# Printrboard.net
KiCad netlist of a schematic drawn in EAGLE
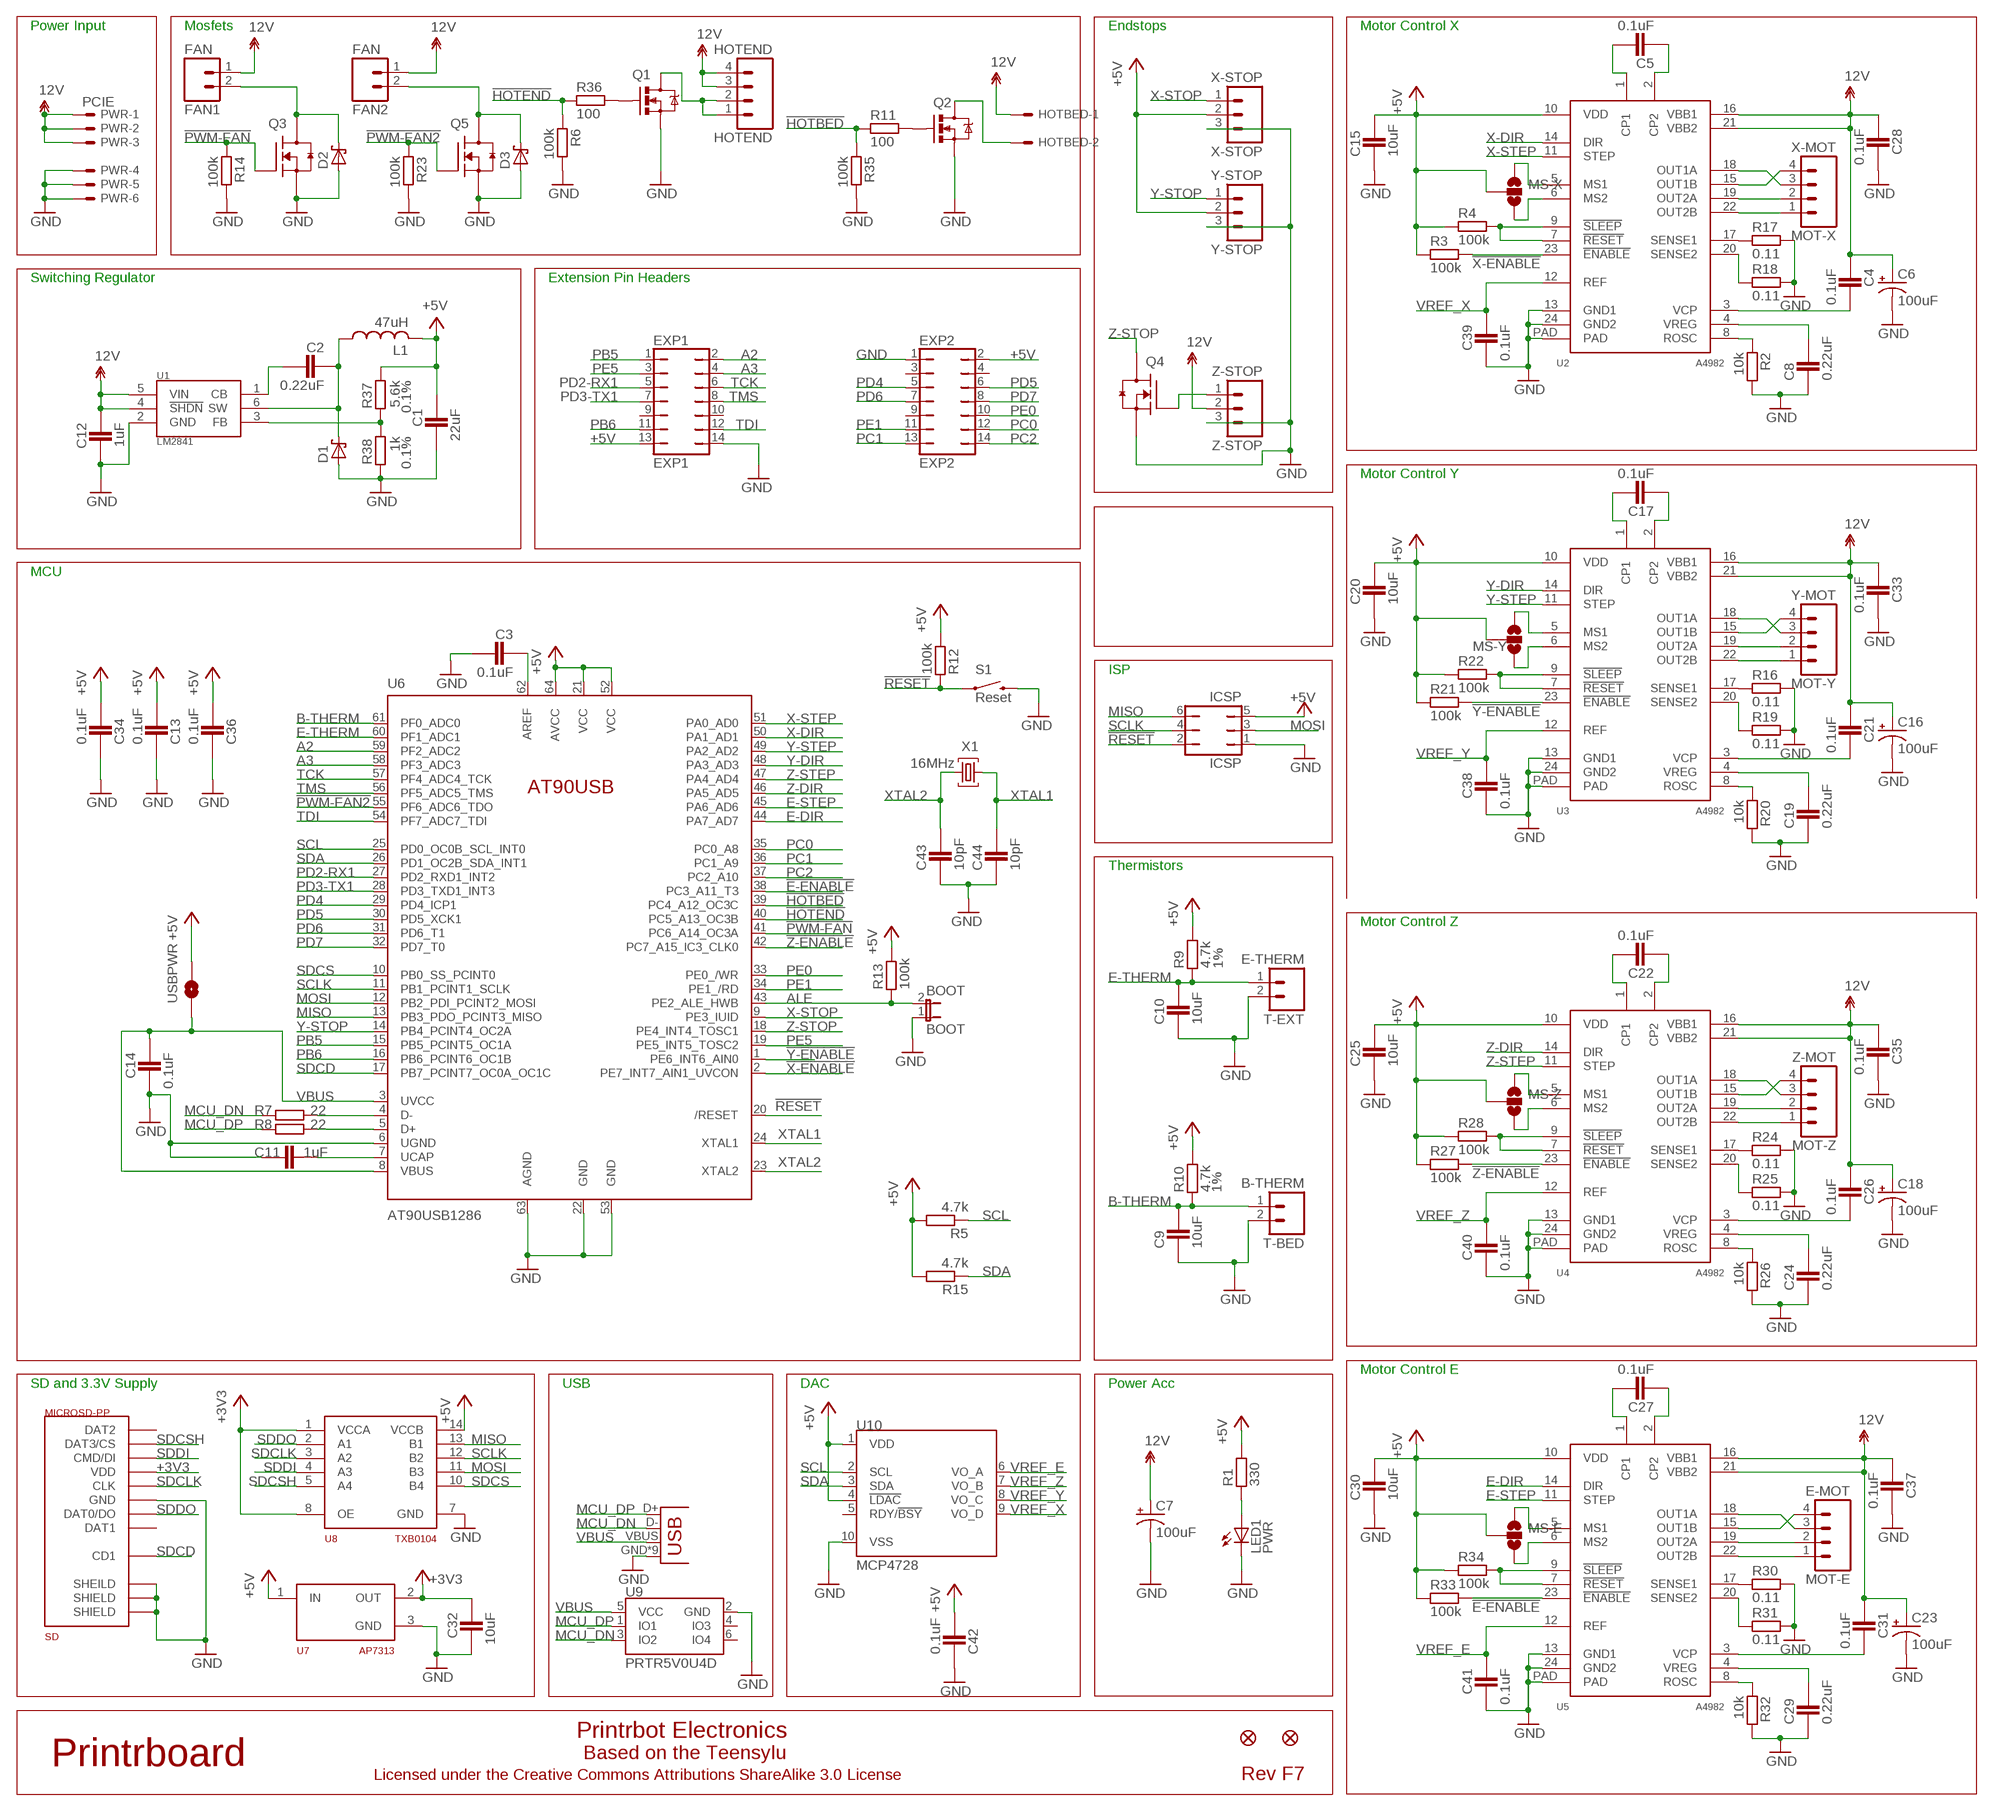
[diagram p0: schematic, sheet 1]

(export (version "E")
  (design (tool "Eeschema 10.0.6"))
  (components
    (comp (ref "BOOT")
      (value "BOOT")
      (footprint "eagle-import:1X02")
      (libsource (lib "eagle-import") (part "JUMPER-2PTH"))
    )
    (comp (ref "C1")
      (value "22uF")
      (footprint "eagle-import:CAPC2012X145AN")
      (libsource (lib "eagle-import") (part "CAPACITOR_0805"))
    )
    (comp (ref "C2")
      (value "0.22uF")
      (footprint "eagle-import:CAPC2012X145AN")
      (libsource (lib "eagle-import") (part "CAPACITOR_0805"))
    )
    (comp (ref "C3")
      (value "0.1uF")
      (footprint "eagle-import:CAPC2012X145AN")
      (libsource (lib "eagle-import") (part "CAPACITOR_0805"))
    )
    (comp (ref "C4")
      (value "0.1uF")
      (footprint "eagle-import:CAPC2012X145AN")
      (libsource (lib "eagle-import") (part "CAPACITOR_0805"))
    )
    (comp (ref "C5")
      (value "0.1uF")
      (footprint "eagle-import:CAPC2012X145AN")
      (libsource (lib "eagle-import") (part "CAPACITOR_0805"))
    )
    (comp (ref "C6")
      (value "100uF")
      (footprint "eagle-import:PANASONIC_D")
      (libsource (lib "eagle-import") (part "CPOL-USD"))
    )
    (comp (ref "C7")
      (value "100uF")
      (footprint "eagle-import:PANASONIC_D")
      (libsource (lib "eagle-import") (part "CPOL-USD"))
    )
    (comp (ref "C8")
      (value "0.22uF")
      (footprint "eagle-import:CAPC2012X145AN")
      (libsource (lib "eagle-import") (part "CAPACITOR_0805"))
    )
    (comp (ref "C9")
      (value "10uF")
      (footprint "eagle-import:CAPC2012X145AN")
      (libsource (lib "eagle-import") (part "CAPACITOR_0805"))
    )
    (comp (ref "C10")
      (value "10uF")
      (footprint "eagle-import:CAPC2012X145AN")
      (libsource (lib "eagle-import") (part "CAPACITOR_0805"))
    )
    (comp (ref "C11")
      (value "1uF")
      (footprint "eagle-import:CAPC2012X145AN")
      (libsource (lib "eagle-import") (part "CAPACITOR_0805"))
    )
    (comp (ref "C12")
      (value "1uF")
      (footprint "eagle-import:CAPC2012X145AN")
      (libsource (lib "eagle-import") (part "CAPACITOR_0805"))
    )
    (comp (ref "C13")
      (value "0.1uF")
      (footprint "eagle-import:CAPC2012X145AN")
      (libsource (lib "eagle-import") (part "CAPACITOR_0805"))
    )
    (comp (ref "C14")
      (value "0.1uF")
      (footprint "eagle-import:CAPC2012X145AN")
      (libsource (lib "eagle-import") (part "CAPACITOR_0805"))
    )
    (comp (ref "C15")
      (value "10uF")
      (footprint "eagle-import:CAPC2012X145AN")
      (libsource (lib "eagle-import") (part "CAPACITOR_0805"))
    )
    (comp (ref "C16")
      (value "100uF")
      (footprint "eagle-import:PANASONIC_D")
      (libsource (lib "eagle-import") (part "CPOL-USD"))
    )
    (comp (ref "C17")
      (value "0.1uF")
      (footprint "eagle-import:CAPC2012X145AN")
      (libsource (lib "eagle-import") (part "CAPACITOR_0805"))
    )
    (comp (ref "C18")
      (value "100uF")
      (footprint "eagle-import:PANASONIC_D")
      (libsource (lib "eagle-import") (part "CPOL-USD"))
    )
    (comp (ref "C19")
      (value "0.22uF")
      (footprint "eagle-import:CAPC2012X145AN")
      (libsource (lib "eagle-import") (part "CAPACITOR_0805"))
    )
    (comp (ref "C20")
      (value "10uF")
      (footprint "eagle-import:CAPC2012X145AN")
      (libsource (lib "eagle-import") (part "CAPACITOR_0805"))
    )
    (comp (ref "C21")
      (value "0.1uF")
      (footprint "eagle-import:CAPC2012X145AN")
      (libsource (lib "eagle-import") (part "CAPACITOR_0805"))
    )
    (comp (ref "C22")
      (value "0.1uF")
      (footprint "eagle-import:CAPC2012X145AN")
      (libsource (lib "eagle-import") (part "CAPACITOR_0805"))
    )
    (comp (ref "C23")
      (value "100uF")
      (footprint "eagle-import:PANASONIC_D")
      (libsource (lib "eagle-import") (part "CPOL-USD"))
    )
    (comp (ref "C24")
      (value "0.22uF")
      (footprint "eagle-import:CAPC2012X145AN")
      (libsource (lib "eagle-import") (part "CAPACITOR_0805"))
    )
    (comp (ref "C25")
      (value "10uF")
      (footprint "eagle-import:CAPC2012X145AN")
      (libsource (lib "eagle-import") (part "CAPACITOR_0805"))
    )
    (comp (ref "C26")
      (value "0.1uF")
      (footprint "eagle-import:CAPC2012X145AN")
      (libsource (lib "eagle-import") (part "CAPACITOR_0805"))
    )
    (comp (ref "C27")
      (value "0.1uF")
      (footprint "eagle-import:CAPC2012X145AN")
      (libsource (lib "eagle-import") (part "CAPACITOR_0805"))
    )
    (comp (ref "C28")
      (value "0.1uF")
      (footprint "eagle-import:CAPC2012X145AN")
      (libsource (lib "eagle-import") (part "CAPACITOR_0805"))
    )
    (comp (ref "C29")
      (value "0.22uF")
      (footprint "eagle-import:CAPC2012X145AN")
      (libsource (lib "eagle-import") (part "CAPACITOR_0805"))
    )
    (comp (ref "C30")
      (value "10uF")
      (footprint "eagle-import:CAPC2012X145AN")
      (libsource (lib "eagle-import") (part "CAPACITOR_0805"))
    )
    (comp (ref "C31")
      (value "0.1uF")
      (footprint "eagle-import:CAPC2012X145AN")
      (libsource (lib "eagle-import") (part "CAPACITOR_0805"))
    )
    (comp (ref "C32")
      (value "10uF")
      (footprint "eagle-import:CAPC2012X145AN")
      (libsource (lib "eagle-import") (part "CAPACITOR_0805"))
    )
    (comp (ref "C33")
      (value "0.1uF")
      (footprint "eagle-import:CAPC2012X145AN")
      (libsource (lib "eagle-import") (part "CAPACITOR_0805"))
    )
    (comp (ref "C34")
      (value "0.1uF")
      (footprint "eagle-import:CAPC2012X145AN")
      (libsource (lib "eagle-import") (part "CAPACITOR_0805"))
    )
    (comp (ref "C35")
      (value "0.1uF")
      (footprint "eagle-import:CAPC2012X145AN")
      (libsource (lib "eagle-import") (part "CAPACITOR_0805"))
    )
    (comp (ref "C36")
      (value "0.1uF")
      (footprint "eagle-import:CAPC2012X145AN")
      (libsource (lib "eagle-import") (part "CAPACITOR_0805"))
    )
    (comp (ref "C37")
      (value "0.1uF")
      (footprint "eagle-import:CAPC2012X145AN")
      (libsource (lib "eagle-import") (part "CAPACITOR_0805"))
    )
    (comp (ref "C38")
      (value "0.1uF")
      (footprint "eagle-import:CAPC2012X145AN")
      (libsource (lib "eagle-import") (part "CAPACITOR_0805"))
    )
    (comp (ref "C39")
      (value "0.1uF")
      (footprint "eagle-import:CAPC2012X145AN")
      (libsource (lib "eagle-import") (part "CAPACITOR_0805"))
    )
    (comp (ref "C40")
      (value "0.1uF")
      (footprint "eagle-import:CAPC2012X145AN")
      (libsource (lib "eagle-import") (part "CAPACITOR_0805"))
    )
    (comp (ref "C41")
      (value "0.1uF")
      (footprint "eagle-import:CAPC2012X145AN")
      (libsource (lib "eagle-import") (part "CAPACITOR_0805"))
    )
    (comp (ref "C42")
      (value "0.1uF")
      (footprint "eagle-import:CAPC2012X145AN")
      (libsource (lib "eagle-import") (part "CAPACITOR_0805"))
    )
    (comp (ref "C43")
      (value "10pF")
      (footprint "eagle-import:CAPC2012X145AN")
      (libsource (lib "eagle-import") (part "CAPACITOR_0805"))
    )
    (comp (ref "C44")
      (value "10pF")
      (footprint "eagle-import:CAPC2012X145AN")
      (libsource (lib "eagle-import") (part "CAPACITOR_0805"))
    )
    (comp (ref "D1")
      (value "SCH-DIODESMA")
      (footprint "eagle-import:SMA")
      (libsource (lib "eagle-import") (part "SCH-DIODESMA"))
    )
    (comp (ref "D2")
      (value "SCH-DIODESMA")
      (footprint "eagle-import:SMA")
      (libsource (lib "eagle-import") (part "SCH-DIODESMA"))
    )
    (comp (ref "D3")
      (value "SCH-DIODESMA")
      (footprint "eagle-import:SMA")
      (libsource (lib "eagle-import") (part "SCH-DIODESMA"))
    )
    (comp (ref "E-MOT")
      (value "MOT-E")
      (footprint "eagle-import:MOLEX-1X4")
      (libsource (lib "eagle-import") (part "M04POLAR"))
    )
    (comp (ref "EXP1")
      (value "EXP1")
      (footprint "eagle-import:JP7Q")
      (libsource (lib "eagle-import") (part "JP7Q"))
    )
    (comp (ref "EXP2")
      (value "EXP2")
      (footprint "eagle-import:JP7Q")
      (libsource (lib "eagle-import") (part "JP7Q"))
    )
    (comp (ref "FAN1")
      (value "FAN")
      (footprint "eagle-import:1X02")
      (libsource (lib "eagle-import") (part "M02PTH"))
    )
    (comp (ref "FAN2")
      (value "FAN")
      (footprint "eagle-import:1X02")
      (libsource (lib "eagle-import") (part "M02PTH"))
    )
    (comp (ref "HOTBED")
      (value "PHOENIX-2POS-5MM-SCREW")
      (footprint "eagle-import:PHOENIX-5MM-2POS")
      (libsource (lib "eagle-import") (part "PHOENIX-2POS-5MM-SCREW"))
    )
    (comp (ref "HOTEND")
      (value "HOTEND")
      (footprint "eagle-import:MOLEX-1X4")
      (libsource (lib "eagle-import") (part "M04POLAR"))
    )
    (comp (ref "ICSP")
      (value "ICSP")
      (footprint "eagle-import:JP3Q")
      (libsource (lib "eagle-import") (part "JP3Q"))
    )
    (comp (ref "JP26")
      (value "FIDUCIAL1X2.5")
      (footprint "eagle-import:FIDUCIAL-1X2.5")
      (libsource (lib "eagle-import") (part "FIDUCIAL1X2.5"))
    )
    (comp (ref "JP33")
      (value "FIDUCIAL1X2.5")
      (footprint "eagle-import:FIDUCIAL-1X2.5")
      (libsource (lib "eagle-import") (part "FIDUCIAL1X2.5"))
    )
    (comp (ref "L1")
      (value "47uH")
      (footprint "eagle-import:SDR1006")
      (libsource (lib "eagle-import") (part "L-US"))
    )
    (comp (ref "LED1")
      (value "PWR")
      (footprint "eagle-import:CHIP-LED0805")
      (libsource (lib "eagle-import") (part "LEDCHIP-LED0805"))
    )
    (comp (ref "MS-E")
      (value "SOLDERJUMPER_2WAYCONNECTED")
      (footprint "eagle-import:SJ_3_CONNECTED")
      (libsource (lib "eagle-import") (part "SOLDERJUMPER_2WAYCONNECTED"))
    )
    (comp (ref "MS-X")
      (value "SOLDERJUMPER_2WAYCONNECTED")
      (footprint "eagle-import:SJ_3_CONNECTED")
      (libsource (lib "eagle-import") (part "SOLDERJUMPER_2WAYCONNECTED"))
    )
    (comp (ref "MS-Y")
      (value "SOLDERJUMPER_2WAYCONNECTED")
      (footprint "eagle-import:SJ_3_CONNECTED")
      (libsource (lib "eagle-import") (part "SOLDERJUMPER_2WAYCONNECTED"))
    )
    (comp (ref "MS-Z")
      (value "SOLDERJUMPER_2WAYCONNECTED")
      (footprint "eagle-import:SJ_3_CONNECTED")
      (libsource (lib "eagle-import") (part "SOLDERJUMPER_2WAYCONNECTED"))
    )
    (comp (ref "PWR")
      (value "PCIE")
      (footprint "eagle-import:5566-6")
      (fields (field (name "MPN") "95566-61002"))
      (libsource (lib "eagle-import") (part "5566-6"))
    )
    (comp (ref "Q1")
      (value "RFP30N06LE")
      (footprint "eagle-import:TO220V")
      (libsource (lib "eagle-import") (part "MOSFET-NCHANNELPTH2"))
    )
    (comp (ref "Q2")
      (value "RFP30N06LE")
      (footprint "eagle-import:TO220V")
      (libsource (lib "eagle-import") (part "MOSFET-NCHANNELPTH2"))
    )
    (comp (ref "Q3")
      (value "RFP30N06LE")
      (footprint "eagle-import:SOT95P280X135-3N")
      (libsource (lib "eagle-import") (part "MOSFET-NCH_SOT-23"))
    )
    (comp (ref "Q4")
      (value "RFP30N06LE")
      (footprint "eagle-import:SOT95P280X135-3N")
      (libsource (lib "eagle-import") (part "MOSFET-NCH_SOT-23"))
    )
    (comp (ref "Q5")
      (value "RFP30N06LE")
      (footprint "eagle-import:SOT95P280X135-3N")
      (libsource (lib "eagle-import") (part "MOSFET-NCH_SOT-23"))
    )
    (comp (ref "R1")
      (value "330")
      (footprint "eagle-import:RESC2012X70N")
      (libsource (lib "eagle-import") (part "RESISTOR_0805"))
    )
    (comp (ref "R2")
      (value "10k")
      (footprint "eagle-import:RESC2012X70N")
      (libsource (lib "eagle-import") (part "RESISTOR_0805"))
    )
    (comp (ref "R3")
      (value "100k")
      (footprint "eagle-import:RESC2012X70N")
      (libsource (lib "eagle-import") (part "RESISTOR_0805"))
    )
    (comp (ref "R4")
      (value "100k")
      (footprint "eagle-import:RESC2012X70N")
      (libsource (lib "eagle-import") (part "RESISTOR_0805"))
    )
    (comp (ref "R5")
      (value "4.7k")
      (footprint "eagle-import:RESC2012X70N")
      (libsource (lib "eagle-import") (part "RESISTOR_0805"))
    )
    (comp (ref "R6")
      (value "100k")
      (footprint "eagle-import:RESC2012X70N")
      (libsource (lib "eagle-import") (part "RESISTOR_0805"))
    )
    (comp (ref "R7")
      (value "22")
      (footprint "eagle-import:RESC2012X70N")
      (libsource (lib "eagle-import") (part "RESISTOR_0805"))
    )
    (comp (ref "R8")
      (value "22")
      (footprint "eagle-import:RESC2012X70N")
      (libsource (lib "eagle-import") (part "RESISTOR_0805"))
    )
    (comp (ref "R9")
      (value "4.7k")
      (footprint "eagle-import:RESC2012X70N")
      (fields (field (name "TOLERANCE") "1%"))
      (libsource (lib "eagle-import") (part "RESISTOR_0805"))
    )
    (comp (ref "R10")
      (value "4.7k")
      (footprint "eagle-import:RESC2012X70N")
      (fields (field (name "TOLERANCE") "1%"))
      (libsource (lib "eagle-import") (part "RESISTOR_0805"))
    )
    (comp (ref "R11")
      (value "100")
      (footprint "eagle-import:RESC2012X70N")
      (libsource (lib "eagle-import") (part "RESISTOR_0805"))
    )
    (comp (ref "R12")
      (value "100k")
      (footprint "eagle-import:RESC2012X70N")
      (libsource (lib "eagle-import") (part "RESISTOR_0805"))
    )
    (comp (ref "R13")
      (value "100k")
      (footprint "eagle-import:RESC2012X70N")
      (libsource (lib "eagle-import") (part "RESISTOR_0805"))
    )
    (comp (ref "R14")
      (value "100k")
      (footprint "eagle-import:RESC2012X70N")
      (libsource (lib "eagle-import") (part "RESISTOR_0805"))
    )
    (comp (ref "R15")
      (value "4.7k")
      (footprint "eagle-import:RESC2012X70N")
      (libsource (lib "eagle-import") (part "RESISTOR_0805"))
    )
    (comp (ref "R16")
      (value "0.11")
      (footprint "eagle-import:RESC2012X70N")
      (libsource (lib "eagle-import") (part "RESISTOR_0805"))
    )
    (comp (ref "R17")
      (value "0.11")
      (footprint "eagle-import:RESC2012X70N")
      (libsource (lib "eagle-import") (part "RESISTOR_0805"))
    )
    (comp (ref "R18")
      (value "0.11")
      (footprint "eagle-import:RESC2012X70N")
      (libsource (lib "eagle-import") (part "RESISTOR_0805"))
    )
    (comp (ref "R19")
      (value "0.11")
      (footprint "eagle-import:RESC2012X70N")
      (libsource (lib "eagle-import") (part "RESISTOR_0805"))
    )
    (comp (ref "R20")
      (value "10k")
      (footprint "eagle-import:RESC2012X70N")
      (libsource (lib "eagle-import") (part "RESISTOR_0805"))
    )
    (comp (ref "R21")
      (value "100k")
      (footprint "eagle-import:RESC2012X70N")
      (libsource (lib "eagle-import") (part "RESISTOR_0805"))
    )
    (comp (ref "R22")
      (value "100k")
      (footprint "eagle-import:RESC2012X70N")
      (libsource (lib "eagle-import") (part "RESISTOR_0805"))
    )
    (comp (ref "R23")
      (value "100k")
      (footprint "eagle-import:RESC2012X70N")
      (libsource (lib "eagle-import") (part "RESISTOR_0805"))
    )
    (comp (ref "R24")
      (value "0.11")
      (footprint "eagle-import:RESC2012X70N")
      (libsource (lib "eagle-import") (part "RESISTOR_0805"))
    )
    (comp (ref "R25")
      (value "0.11")
      (footprint "eagle-import:RESC2012X70N")
      (libsource (lib "eagle-import") (part "RESISTOR_0805"))
    )
    (comp (ref "R26")
      (value "10k")
      (footprint "eagle-import:RESC2012X70N")
      (libsource (lib "eagle-import") (part "RESISTOR_0805"))
    )
    (comp (ref "R27")
      (value "100k")
      (footprint "eagle-import:RESC2012X70N")
      (libsource (lib "eagle-import") (part "RESISTOR_0805"))
    )
    (comp (ref "R28")
      (value "100k")
      (footprint "eagle-import:RESC2012X70N")
      (libsource (lib "eagle-import") (part "RESISTOR_0805"))
    )
    (comp (ref "R30")
      (value "0.11")
      (footprint "eagle-import:RESC2012X70N")
      (libsource (lib "eagle-import") (part "RESISTOR_0805"))
    )
    (comp (ref "R31")
      (value "0.11")
      (footprint "eagle-import:RESC2012X70N")
      (libsource (lib "eagle-import") (part "RESISTOR_0805"))
    )
    (comp (ref "R32")
      (value "10k")
      (footprint "eagle-import:RESC2012X70N")
      (libsource (lib "eagle-import") (part "RESISTOR_0805"))
    )
    (comp (ref "R33")
      (value "100k")
      (footprint "eagle-import:RESC2012X70N")
      (libsource (lib "eagle-import") (part "RESISTOR_0805"))
    )
    (comp (ref "R34")
      (value "100k")
      (footprint "eagle-import:RESC2012X70N")
      (libsource (lib "eagle-import") (part "RESISTOR_0805"))
    )
    (comp (ref "R35")
      (value "100k")
      (footprint "eagle-import:RESC2012X70N")
      (libsource (lib "eagle-import") (part "RESISTOR_0805"))
    )
    (comp (ref "R36")
      (value "100")
      (footprint "eagle-import:RESC2012X70N")
      (libsource (lib "eagle-import") (part "RESISTOR_0805"))
    )
    (comp (ref "R37")
      (value "5.6k")
      (footprint "eagle-import:RESC2012X70N")
      (fields (field (name "TOLERANCE") "0.1%"))
      (libsource (lib "eagle-import") (part "RESISTOR_0805"))
    )
    (comp (ref "R38")
      (value "1k")
      (footprint "eagle-import:RESC2012X70N")
      (fields (field (name "TOLERANCE") "0.1%"))
      (libsource (lib "eagle-import") (part "RESISTOR_0805"))
    )
    (comp (ref "S1")
      (value "Reset")
      (footprint "eagle-import:TACTILE_SWITCH_TALL")
      (libsource (lib "eagle-import") (part "SWITCH-MOMENTARY-2"))
    )
    (comp (ref "SD")
      (value "MICROSD-PP")
      (footprint "eagle-import:USD-101-00660-68-6")
      (libsource (lib "eagle-import") (part "MICROSD-PP"))
    )
    (comp (ref "T-BED")
      (value "B-THERM")
      (footprint "eagle-import:1X02")
      (libsource (lib "eagle-import") (part "M02PTH"))
    )
    (comp (ref "T-EXT")
      (value "E-THERM")
      (footprint "eagle-import:1X02")
      (libsource (lib "eagle-import") (part "M02PTH"))
    )
    (comp (ref "U1")
      (value "LM2841")
      (footprint "eagle-import:TSOT6")
      (libsource (lib "eagle-import") (part "LM2841"))
    )
    (comp (ref "U2")
      (value "A4982")
      (footprint "eagle-import:TSSOP-24")
      (libsource (lib "eagle-import") (part "A4982"))
    )
    (comp (ref "U3")
      (value "A4982")
      (footprint "eagle-import:TSSOP-24")
      (libsource (lib "eagle-import") (part "A4982"))
    )
    (comp (ref "U4")
      (value "A4982")
      (footprint "eagle-import:TSSOP-24")
      (libsource (lib "eagle-import") (part "A4982"))
    )
    (comp (ref "U5")
      (value "A4982")
      (footprint "eagle-import:TSSOP-24")
      (libsource (lib "eagle-import") (part "A4982"))
    )
    (comp (ref "U6")
      (value "AT90USB1286")
      (footprint "eagle-import:TQFP64-2")
      (libsource (lib "eagle-import") (part "AT90USB"))
    )
    (comp (ref "U7")
      (value "AP7313")
      (footprint "eagle-import:SOT23C")
      (libsource (lib "eagle-import") (part "AP7313"))
    )
    (comp (ref "U8")
      (value "TXB0104")
      (footprint "eagle-import:TSSOP14")
      (libsource (lib "eagle-import") (part "TXB0104"))
    )
    (comp (ref "U9")
      (value "PRTR5V0U4D")
      (footprint "eagle-import:SOT23-6")
      (libsource (lib "eagle-import") (part "PRTR5V0U4D"))
    )
    (comp (ref "U10")
      (value "MCP4728")
      (footprint "eagle-import:MSOP10")
      (libsource (lib "eagle-import") (part "MCP4728"))
    )
    (comp (ref "USB-M")
      (value "USB-MICRO-PTH")
      (footprint "eagle-import:USB-MICROB-PTH")
      (libsource (lib "eagle-import") (part "USB-MICRO-PTH"))
    )
    (comp (ref "USBPWR")
      (value "SOLDERJUMPERNO")
      (footprint "eagle-import:SJ_2S-NO")
      (libsource (lib "eagle-import") (part "SOLDERJUMPERNO"))
    )
    (comp (ref "X-MOT")
      (value "MOT-X")
      (footprint "eagle-import:MOLEX-1X4")
      (libsource (lib "eagle-import") (part "M04POLAR"))
    )
    (comp (ref "X-STOP")
      (value "X-STOP")
      (footprint "eagle-import:MOLEX-1X3")
      (libsource (lib "eagle-import") (part "M03POLAR"))
    )
    (comp (ref "X1")
      (value "16MHz")
      (footprint "eagle-import:NDK-XTAL")
      (libsource (lib "eagle-import") (part "XTAL"))
    )
    (comp (ref "Y-MOT")
      (value "MOT-Y")
      (footprint "eagle-import:MOLEX-1X4")
      (libsource (lib "eagle-import") (part "M04POLAR"))
    )
    (comp (ref "Y-STOP")
      (value "Y-STOP")
      (footprint "eagle-import:MOLEX-1X3")
      (libsource (lib "eagle-import") (part "M03POLAR"))
    )
    (comp (ref "Z-MOT")
      (value "MOT-Z")
      (footprint "eagle-import:MOLEX-1X4")
      (libsource (lib "eagle-import") (part "M04POLAR"))
    )
    (comp (ref "Z-STOP")
      (value "Z-STOP")
      (footprint "eagle-import:MOLEX-1X3")
      (libsource (lib "eagle-import") (part "M03POLAR"))
    )
  )
  (nets
    (net (code "1") (name "+3V3") (class "Default")
      (node (ref "C32") (pin "1") (pinfunction "1_1") (pintype "passive"))
      (node (ref "SD") (pin "P$4") (pinfunction "VDD_P$4") (pintype "power_in"))
      (node (ref "U7") (pin "2") (pinfunction "OUT_2") (pintype "power_in"))
      (node (ref "U8") (pin "1") (pinfunction "VCCA_1") (pintype "power_in"))
      (node (ref "U8") (pin "8") (pinfunction "OE_8") (pintype "input"))
    )
    (net (code "2") (name "+5V") (class "Default")
      (node (ref "C1") (pin "1") (pinfunction "1_1") (pintype "passive"))
      (node (ref "C13") (pin "2") (pinfunction "2_2") (pintype "passive"))
      (node (ref "C15") (pin "2") (pinfunction "2_2") (pintype "passive"))
      (node (ref "C20") (pin "2") (pinfunction "2_2") (pintype "passive"))
      (node (ref "C25") (pin "2") (pinfunction "2_2") (pintype "passive"))
      (node (ref "C30") (pin "2") (pinfunction "2_2") (pintype "passive"))
      (node (ref "C34") (pin "2") (pinfunction "2_2") (pintype "passive"))
      (node (ref "C36") (pin "2") (pinfunction "2_2") (pintype "passive"))
      (node (ref "C42") (pin "2") (pinfunction "2_2") (pintype "passive"))
      (node (ref "EXP1") (pin "13") (pinfunction "13_13") (pintype "passive"))
      (node (ref "EXP2") (pin "2") (pinfunction "2_2") (pintype "passive"))
      (node (ref "ICSP") (pin "5") (pinfunction "5_5") (pintype "passive"))
      (node (ref "L1") (pin "P$2") (pinfunction "2_P$2") (pintype "passive"))
      (node (ref "MS-E") (pin "2") (pinfunction "2_2") (pintype "passive"))
      (node (ref "MS-X") (pin "2") (pinfunction "2_2") (pintype "passive"))
      (node (ref "MS-Y") (pin "2") (pinfunction "2_2") (pintype "passive"))
      (node (ref "MS-Z") (pin "2") (pinfunction "2_2") (pintype "passive"))
      (node (ref "R1") (pin "2") (pinfunction "2_2") (pintype "passive"))
      (node (ref "R10") (pin "2") (pinfunction "2_2") (pintype "passive"))
      (node (ref "R12") (pin "2") (pinfunction "2_2") (pintype "passive"))
      (node (ref "R13") (pin "2") (pinfunction "2_2") (pintype "passive"))
      (node (ref "R15") (pin "2") (pinfunction "2_2") (pintype "passive"))
      (node (ref "R21") (pin "1") (pinfunction "1_1") (pintype "passive"))
      (node (ref "R22") (pin "1") (pinfunction "1_1") (pintype "passive"))
      (node (ref "R27") (pin "1") (pinfunction "1_1") (pintype "passive"))
      (node (ref "R28") (pin "1") (pinfunction "1_1") (pintype "passive"))
      (node (ref "R3") (pin "1") (pinfunction "1_1") (pintype "passive"))
      (node (ref "R33") (pin "1") (pinfunction "1_1") (pintype "passive"))
      (node (ref "R34") (pin "1") (pinfunction "1_1") (pintype "passive"))
      (node (ref "R37") (pin "1") (pinfunction "1_1") (pintype "passive"))
      (node (ref "R4") (pin "1") (pinfunction "1_1") (pintype "passive"))
      (node (ref "R5") (pin "2") (pinfunction "2_2") (pintype "passive"))
      (node (ref "R9") (pin "2") (pinfunction "2_2") (pintype "passive"))
      (node (ref "U10") (pin "1") (pinfunction "VDD_1") (pintype "power_in"))
      (node (ref "U10") (pin "4") (pinfunction "~{LDAC}_4") (pintype "input"))
      (node (ref "U2") (pin "10") (pinfunction "VDD_10") (pintype "power_in"))
      (node (ref "U3") (pin "10") (pinfunction "VDD_10") (pintype "power_in"))
      (node (ref "U4") (pin "10") (pinfunction "VDD_10") (pintype "power_in"))
      (node (ref "U5") (pin "10") (pinfunction "VDD_10") (pintype "power_in"))
      (node (ref "U6") (pin "21") (pinfunction "VCC_21") (pintype "power_in"))
      (node (ref "U6") (pin "52") (pinfunction "VCC_52") (pintype "power_in"))
      (node (ref "U6") (pin "64") (pinfunction "AVCC_64") (pintype "power_in"))
      (node (ref "U7") (pin "1") (pinfunction "IN_1") (pintype "power_in"))
      (node (ref "U8") (pin "14") (pinfunction "VCCB_14") (pintype "power_in"))
      (node (ref "USBPWR") (pin "2") (pinfunction "2_2") (pintype "passive"))
      (node (ref "X-STOP") (pin "2") (pinfunction "2_2") (pintype "passive"))
      (node (ref "Y-STOP") (pin "2") (pinfunction "2_2") (pintype "passive"))
    )
    (net (code "3") (name "/A2") (class "Default")
      (node (ref "EXP1") (pin "2") (pinfunction "2_2") (pintype "passive"))
      (node (ref "U6") (pin "59") (pinfunction "PF2_ADC2_59") (pintype "bidirectional"))
    )
    (net (code "4") (name "/A3") (class "Default")
      (node (ref "EXP1") (pin "4") (pinfunction "4_4") (pintype "passive"))
      (node (ref "U6") (pin "58") (pinfunction "PF3_ADC3_58") (pintype "bidirectional"))
    )
    (net (code "5") (name "/ALE") (class "Default")
      (node (ref "BOOT") (pin "2") (pinfunction "2_2") (pintype "passive"))
      (node (ref "R13") (pin "1") (pinfunction "1_1") (pintype "passive"))
      (node (ref "U6") (pin "43") (pinfunction "PE2_ALE_HWB_43") (pintype "bidirectional"))
    )
    (net (code "6") (name "/B-THERM") (class "Default")
      (node (ref "C9") (pin "2") (pinfunction "2_2") (pintype "passive"))
      (node (ref "R10") (pin "1") (pinfunction "1_1") (pintype "passive"))
      (node (ref "T-BED") (pin "1") (pinfunction "1_1") (pintype "passive"))
      (node (ref "U6") (pin "61") (pinfunction "PF0_ADC0_61") (pintype "bidirectional"))
    )
    (net (code "7") (name "/E-DIR") (class "Default")
      (node (ref "U5") (pin "14") (pinfunction "DIR_14") (pintype "input"))
      (node (ref "U6") (pin "44") (pinfunction "PA7_AD7_44") (pintype "bidirectional"))
    )
    (net (code "8") (name "/E-STEP") (class "Default")
      (node (ref "U5") (pin "11") (pinfunction "STEP_11") (pintype "input"))
      (node (ref "U6") (pin "45") (pinfunction "PA6_AD6_45") (pintype "bidirectional"))
    )
    (net (code "9") (name "/E-THERM") (class "Default")
      (node (ref "C10") (pin "2") (pinfunction "2_2") (pintype "passive"))
      (node (ref "R9") (pin "1") (pinfunction "1_1") (pintype "passive"))
      (node (ref "T-EXT") (pin "1") (pinfunction "1_1") (pintype "passive"))
      (node (ref "U6") (pin "60") (pinfunction "PF1_ADC1_60") (pintype "bidirectional"))
    )
    (net (code "10") (name "/MCU_DN") (class "Default")
      (node (ref "R7") (pin "1") (pinfunction "1_1") (pintype "passive"))
      (node (ref "U9") (pin "3") (pinfunction "IO2_3") (pintype "bidirectional"))
      (node (ref "USB-M") (pin "D-") (pinfunction "D-_D-") (pintype "bidirectional"))
    )
    (net (code "11") (name "/MCU_DP") (class "Default")
      (node (ref "R8") (pin "1") (pinfunction "1_1") (pintype "passive"))
      (node (ref "U9") (pin "1") (pinfunction "IO1_1") (pintype "bidirectional"))
      (node (ref "USB-M") (pin "D+") (pinfunction "D+_D+") (pintype "bidirectional"))
    )
    (net (code "12") (name "/MISO") (class "Default")
      (node (ref "ICSP") (pin "6") (pinfunction "6_6") (pintype "passive"))
      (node (ref "U6") (pin "13") (pinfunction "PB3_PDO_PCINT3_MISO_13") (pintype "bidirectional"))
      (node (ref "U8") (pin "13") (pinfunction "B1_13") (pintype "bidirectional"))
    )
    (net (code "13") (name "/MOSI") (class "Default")
      (node (ref "ICSP") (pin "3") (pinfunction "3_3") (pintype "passive"))
      (node (ref "U6") (pin "12") (pinfunction "PB2_PDI_PCINT2_MOSI_12") (pintype "bidirectional"))
      (node (ref "U8") (pin "11") (pinfunction "B3_11") (pintype "bidirectional"))
    )
    (net (code "14") (name "/PB5") (class "Default")
      (node (ref "EXP1") (pin "1") (pinfunction "1_1") (pintype "passive"))
      (node (ref "U6") (pin "15") (pinfunction "PB5_PCINT5_OC1A_15") (pintype "bidirectional"))
    )
    (net (code "15") (name "/PB6") (class "Default")
      (node (ref "EXP1") (pin "11") (pinfunction "11_11") (pintype "passive"))
      (node (ref "U6") (pin "16") (pinfunction "PB6_PCINT6_OC1B_16") (pintype "bidirectional"))
    )
    (net (code "16") (name "/PC0") (class "Default")
      (node (ref "EXP2") (pin "12") (pinfunction "12_12") (pintype "passive"))
      (node (ref "U6") (pin "35") (pinfunction "PC0_A8_35") (pintype "bidirectional"))
    )
    (net (code "17") (name "/PC1") (class "Default")
      (node (ref "EXP2") (pin "13") (pinfunction "13_13") (pintype "passive"))
      (node (ref "U6") (pin "36") (pinfunction "PC1_A9_36") (pintype "bidirectional"))
    )
    (net (code "18") (name "/PC2") (class "Default")
      (node (ref "EXP2") (pin "14") (pinfunction "14_14") (pintype "passive"))
      (node (ref "U6") (pin "37") (pinfunction "PC2_A10_37") (pintype "bidirectional"))
    )
    (net (code "19") (name "/PD2-RX1") (class "Default")
      (node (ref "EXP1") (pin "5") (pinfunction "5_5") (pintype "passive"))
      (node (ref "U6") (pin "27") (pinfunction "PD2_RXD1_INT2_27") (pintype "bidirectional"))
    )
    (net (code "20") (name "/PD3-TX1") (class "Default")
      (node (ref "EXP1") (pin "7") (pinfunction "7_7") (pintype "passive"))
      (node (ref "U6") (pin "28") (pinfunction "PD3_TXD1_INT3_28") (pintype "bidirectional"))
    )
    (net (code "21") (name "/PD4") (class "Default")
      (node (ref "EXP2") (pin "5") (pinfunction "5_5") (pintype "passive"))
      (node (ref "U6") (pin "29") (pinfunction "PD4_ICP1_29") (pintype "bidirectional"))
    )
    (net (code "22") (name "/PD5") (class "Default")
      (node (ref "EXP2") (pin "6") (pinfunction "6_6") (pintype "passive"))
      (node (ref "U6") (pin "30") (pinfunction "PD5_XCK1_30") (pintype "bidirectional"))
    )
    (net (code "23") (name "/PD6") (class "Default")
      (node (ref "EXP2") (pin "7") (pinfunction "7_7") (pintype "passive"))
      (node (ref "U6") (pin "31") (pinfunction "PD6_T1_31") (pintype "bidirectional"))
    )
    (net (code "24") (name "/PD7") (class "Default")
      (node (ref "EXP2") (pin "8") (pinfunction "8_8") (pintype "passive"))
      (node (ref "U6") (pin "32") (pinfunction "PD7_T0_32") (pintype "bidirectional"))
    )
    (net (code "25") (name "/PE0") (class "Default")
      (node (ref "EXP2") (pin "10") (pinfunction "10_10") (pintype "passive"))
      (node (ref "U6") (pin "33") (pinfunction "PE0_/WR_33") (pintype "bidirectional"))
    )
    (net (code "26") (name "/PE1") (class "Default")
      (node (ref "EXP2") (pin "11") (pinfunction "11_11") (pintype "passive"))
      (node (ref "U6") (pin "34") (pinfunction "PE1_/RD_34") (pintype "bidirectional"))
    )
    (net (code "27") (name "/PE5") (class "Default")
      (node (ref "EXP1") (pin "3") (pinfunction "3_3") (pintype "passive"))
      (node (ref "U6") (pin "19") (pinfunction "PE5_INT5_TOSC2_19") (pintype "bidirectional"))
    )
    (net (code "28") (name "/SCL") (class "Default")
      (node (ref "R5") (pin "1") (pinfunction "1_1") (pintype "passive"))
      (node (ref "U10") (pin "2") (pinfunction "SCL_2") (pintype "input"))
      (node (ref "U6") (pin "25") (pinfunction "PD0_OC0B_SCL_INT0_25") (pintype "bidirectional"))
    )
    (net (code "29") (name "/SCLK") (class "Default")
      (node (ref "ICSP") (pin "4") (pinfunction "4_4") (pintype "passive"))
      (node (ref "U6") (pin "11") (pinfunction "PB1_PCINT1_SCLK_11") (pintype "bidirectional"))
      (node (ref "U8") (pin "12") (pinfunction "B2_12") (pintype "bidirectional"))
    )
    (net (code "30") (name "/SDA") (class "Default")
      (node (ref "R15") (pin "1") (pinfunction "1_1") (pintype "passive"))
      (node (ref "U10") (pin "3") (pinfunction "SDA_3") (pintype "bidirectional"))
      (node (ref "U6") (pin "26") (pinfunction "PD1_OC2B_SDA_INT1_26") (pintype "bidirectional"))
    )
    (net (code "31") (name "/SDCD") (class "Default")
      (node (ref "SD") (pin "CD") (pinfunction "CD1_CD") (pintype "bidirectional"))
      (node (ref "U6") (pin "17") (pinfunction "PB7_PCINT7_OC0A_OC1C_17") (pintype "bidirectional"))
    )
    (net (code "32") (name "/SDCLK") (class "Default")
      (node (ref "SD") (pin "P$5") (pinfunction "CLK_P$5") (pintype "input"))
      (node (ref "U8") (pin "3") (pinfunction "A2_3") (pintype "bidirectional"))
    )
    (net (code "33") (name "/SDCS") (class "Default")
      (node (ref "U6") (pin "10") (pinfunction "PB0_SS_PCINT0_10") (pintype "bidirectional"))
      (node (ref "U8") (pin "10") (pinfunction "B4_10") (pintype "bidirectional"))
    )
    (net (code "34") (name "/SDCSH") (class "Default")
      (node (ref "SD") (pin "P$2") (pinfunction "DAT3/CS_P$2") (pintype "bidirectional"))
      (node (ref "U8") (pin "5") (pinfunction "A4_5") (pintype "bidirectional"))
    )
    (net (code "35") (name "/SDDI") (class "Default")
      (node (ref "SD") (pin "P$3") (pinfunction "CMD/DI_P$3") (pintype "input"))
      (node (ref "U8") (pin "4") (pinfunction "A3_4") (pintype "bidirectional"))
    )
    (net (code "36") (name "/SDDO") (class "Default")
      (node (ref "SD") (pin "P$7") (pinfunction "DAT0/DO_P$7") (pintype "bidirectional"))
      (node (ref "U8") (pin "2") (pinfunction "A1_2") (pintype "bidirectional"))
    )
    (net (code "37") (name "/TCK") (class "Default")
      (node (ref "EXP1") (pin "6") (pinfunction "6_6") (pintype "passive"))
      (node (ref "U6") (pin "57") (pinfunction "PF4_ADC4_TCK_57") (pintype "bidirectional"))
    )
    (net (code "38") (name "/TDI") (class "Default")
      (node (ref "EXP1") (pin "12") (pinfunction "12_12") (pintype "passive"))
      (node (ref "U6") (pin "54") (pinfunction "PF7_ADC7_TDI_54") (pintype "bidirectional"))
    )
    (net (code "39") (name "/TMS") (class "Default")
      (node (ref "EXP1") (pin "8") (pinfunction "8_8") (pintype "passive"))
      (node (ref "U6") (pin "56") (pinfunction "PF5_ADC5_TMS_56") (pintype "bidirectional"))
    )
    (net (code "40") (name "/VBUS") (class "Default")
      (node (ref "C14") (pin "1") (pinfunction "1_1") (pintype "passive"))
      (node (ref "U6") (pin "3") (pinfunction "UVCC_3") (pintype "power_in"))
      (node (ref "U6") (pin "8") (pinfunction "VBUS_8") (pintype "bidirectional"))
      (node (ref "U9") (pin "5") (pinfunction "VCC_5") (pintype "power_in"))
      (node (ref "USB-M") (pin "VBUS") (pinfunction "VBUS_VBUS") (pintype "bidirectional"))
      (node (ref "USBPWR") (pin "1") (pinfunction "1_1") (pintype "passive"))
    )
    (net (code "41") (name "/VREF_E") (class "Default")
      (node (ref "C41") (pin "1") (pinfunction "1_1") (pintype "passive"))
      (node (ref "U10") (pin "6") (pinfunction "VO_A_6") (pintype "output"))
      (node (ref "U5") (pin "12") (pinfunction "REF_12") (pintype "input"))
    )
    (net (code "42") (name "/VREF_X") (class "Default")
      (node (ref "C39") (pin "1") (pinfunction "1_1") (pintype "passive"))
      (node (ref "U10") (pin "9") (pinfunction "VO_D_9") (pintype "output"))
      (node (ref "U2") (pin "12") (pinfunction "REF_12") (pintype "input"))
    )
    (net (code "43") (name "/VREF_Y") (class "Default")
      (node (ref "C38") (pin "1") (pinfunction "1_1") (pintype "passive"))
      (node (ref "U10") (pin "8") (pinfunction "VO_C_8") (pintype "output"))
      (node (ref "U3") (pin "12") (pinfunction "REF_12") (pintype "input"))
    )
    (net (code "44") (name "/VREF_Z") (class "Default")
      (node (ref "C40") (pin "1") (pinfunction "1_1") (pintype "passive"))
      (node (ref "U10") (pin "7") (pinfunction "VO_B_7") (pintype "output"))
      (node (ref "U4") (pin "12") (pinfunction "REF_12") (pintype "input"))
    )
    (net (code "45") (name "/X-DIR") (class "Default")
      (node (ref "U2") (pin "14") (pinfunction "DIR_14") (pintype "input"))
      (node (ref "U6") (pin "50") (pinfunction "PA1_AD1_50") (pintype "bidirectional"))
    )
    (net (code "46") (name "/X-STEP") (class "Default")
      (node (ref "U2") (pin "11") (pinfunction "STEP_11") (pintype "input"))
      (node (ref "U6") (pin "51") (pinfunction "PA0_AD0_51") (pintype "bidirectional"))
    )
    (net (code "47") (name "/X-STOP") (class "Default")
      (node (ref "U6") (pin "9") (pinfunction "PE3_IUID_9") (pintype "bidirectional"))
      (node (ref "X-STOP") (pin "1") (pinfunction "1_1") (pintype "passive"))
    )
    (net (code "48") (name "/XTAL1") (class "Default")
      (node (ref "C44") (pin "2") (pinfunction "2_2") (pintype "passive"))
      (node (ref "U6") (pin "24") (pinfunction "XTAL1_24") (pintype "passive"))
      (node (ref "X1") (pin "P$1") (pinfunction "1_P$1") (pintype "passive"))
    )
    (net (code "49") (name "/XTAL2") (class "Default")
      (node (ref "C43") (pin "2") (pinfunction "2_2") (pintype "passive"))
      (node (ref "U6") (pin "23") (pinfunction "XTAL2_23") (pintype "passive"))
      (node (ref "X1") (pin "P$2") (pinfunction "2_P$2") (pintype "passive"))
    )
    (net (code "50") (name "/Y-DIR") (class "Default")
      (node (ref "U3") (pin "14") (pinfunction "DIR_14") (pintype "input"))
      (node (ref "U6") (pin "48") (pinfunction "PA3_AD3_48") (pintype "bidirectional"))
    )
    (net (code "51") (name "/Y-STEP") (class "Default")
      (node (ref "U3") (pin "11") (pinfunction "STEP_11") (pintype "input"))
      (node (ref "U6") (pin "49") (pinfunction "PA2_AD2_49") (pintype "bidirectional"))
    )
    (net (code "52") (name "/Y-STOP") (class "Default")
      (node (ref "U6") (pin "14") (pinfunction "PB4_PCINT4_OC2A_14") (pintype "bidirectional"))
      (node (ref "Y-STOP") (pin "1") (pinfunction "1_1") (pintype "passive"))
    )
    (net (code "53") (name "/Z-DIR") (class "Default")
      (node (ref "U4") (pin "14") (pinfunction "DIR_14") (pintype "input"))
      (node (ref "U6") (pin "46") (pinfunction "PA5_AD5_46") (pintype "bidirectional"))
    )
    (net (code "54") (name "/Z-STEP") (class "Default")
      (node (ref "U4") (pin "11") (pinfunction "STEP_11") (pintype "input"))
      (node (ref "U6") (pin "47") (pinfunction "PA4_AD4_47") (pintype "bidirectional"))
    )
    (net (code "55") (name "/Z-STOP") (class "Default")
      (node (ref "Q4") (pin "3") (pinfunction "D_3") (pintype "passive"))
      (node (ref "U6") (pin "18") (pinfunction "PE4_INT4_TOSC1_18") (pintype "bidirectional"))
    )
    (net (code "56") (name "/~{E-ENABLE}") (class "Default")
      (node (ref "R33") (pin "2") (pinfunction "2_2") (pintype "passive"))
      (node (ref "U5") (pin "23") (pinfunction "~{ENABLE}_23") (pintype "input"))
      (node (ref "U6") (pin "38") (pinfunction "PC3_A11_T3_38") (pintype "bidirectional"))
    )
    (net (code "57") (name "/~{HOTBED}") (class "Default")
      (node (ref "R11") (pin "1") (pinfunction "1_1") (pintype "passive"))
      (node (ref "R35") (pin "1") (pinfunction "1_1") (pintype "passive"))
      (node (ref "U6") (pin "39") (pinfunction "PC4_A12_OC3C_39") (pintype "bidirectional"))
    )
    (net (code "58") (name "/~{HOTEND}") (class "Default")
      (node (ref "R36") (pin "1") (pinfunction "1_1") (pintype "passive"))
      (node (ref "R6") (pin "1") (pinfunction "1_1") (pintype "passive"))
      (node (ref "U6") (pin "40") (pinfunction "PC5_A13_OC3B_40") (pintype "bidirectional"))
    )
    (net (code "59") (name "/~{PWM-FAN2}") (class "Default")
      (node (ref "Q5") (pin "1") (pinfunction "G_1") (pintype "passive"))
      (node (ref "R23") (pin "1") (pinfunction "1_1") (pintype "passive"))
      (node (ref "U6") (pin "55") (pinfunction "PF6_ADC6_TDO_55") (pintype "bidirectional"))
    )
    (net (code "60") (name "/~{PWM-FAN}") (class "Default")
      (node (ref "Q3") (pin "1") (pinfunction "G_1") (pintype "passive"))
      (node (ref "R14") (pin "1") (pinfunction "1_1") (pintype "passive"))
      (node (ref "U6") (pin "41") (pinfunction "PC6_A14_OC3A_41") (pintype "bidirectional"))
    )
    (net (code "61") (name "/~{RESET}") (class "Default")
      (node (ref "ICSP") (pin "2") (pinfunction "2_2") (pintype "passive"))
      (node (ref "R12") (pin "1") (pinfunction "1_1") (pintype "passive"))
      (node (ref "S1") (pin "A2") (pinfunction "1_A2") (pintype "passive"))
      (node (ref "U6") (pin "20") (pinfunction "/RESET_20") (pintype "bidirectional"))
    )
    (net (code "62") (name "/~{X-ENABLE}") (class "Default")
      (node (ref "R3") (pin "2") (pinfunction "2_2") (pintype "passive"))
      (node (ref "U2") (pin "23") (pinfunction "~{ENABLE}_23") (pintype "input"))
      (node (ref "U6") (pin "2") (pinfunction "PE7_INT7_AIN1_UVCON_2") (pintype "bidirectional"))
    )
    (net (code "63") (name "/~{Y-ENABLE}") (class "Default")
      (node (ref "R21") (pin "2") (pinfunction "2_2") (pintype "passive"))
      (node (ref "U3") (pin "23") (pinfunction "~{ENABLE}_23") (pintype "input"))
      (node (ref "U6") (pin "1") (pinfunction "PE6_INT6_AIN0_1") (pintype "bidirectional"))
    )
    (net (code "64") (name "/~{Z-ENABLE}") (class "Default")
      (node (ref "R27") (pin "2") (pinfunction "2_2") (pintype "passive"))
      (node (ref "U4") (pin "23") (pinfunction "~{ENABLE}_23") (pintype "input"))
      (node (ref "U6") (pin "42") (pinfunction "PC7_A15_IC3_CLK0_42") (pintype "bidirectional"))
    )
    (net (code "65") (name "12V") (class "Default")
      (node (ref "C12") (pin "1") (pinfunction "1_1") (pintype "passive"))
      (node (ref "C16") (pin "+") (pinfunction "+_+") (pintype "passive"))
      (node (ref "C18") (pin "+") (pinfunction "+_+") (pintype "passive"))
      (node (ref "C21") (pin "1") (pinfunction "1_1") (pintype "passive"))
      (node (ref "C23") (pin "+") (pinfunction "+_+") (pintype "passive"))
      (node (ref "C26") (pin "1") (pinfunction "1_1") (pintype "passive"))
      (node (ref "C28") (pin "1") (pinfunction "1_1") (pintype "passive"))
      (node (ref "C31") (pin "1") (pinfunction "1_1") (pintype "passive"))
      (node (ref "C33") (pin "1") (pinfunction "1_1") (pintype "passive"))
      (node (ref "C35") (pin "1") (pinfunction "1_1") (pintype "passive"))
      (node (ref "C37") (pin "1") (pinfunction "1_1") (pintype "passive"))
      (node (ref "C4") (pin "1") (pinfunction "1_1") (pintype "passive"))
      (node (ref "C6") (pin "+") (pinfunction "+_+") (pintype "passive"))
      (node (ref "C7") (pin "+") (pinfunction "+_+") (pintype "passive"))
      (node (ref "FAN1") (pin "1") (pinfunction "1_1") (pintype "passive"))
      (node (ref "FAN2") (pin "1") (pinfunction "1_1") (pintype "passive"))
      (node (ref "HOTBED") (pin "P$1") (pinfunction "S_P$1") (pintype "passive"))
      (node (ref "HOTEND") (pin "3") (pinfunction "3_3") (pintype "passive"))
      (node (ref "HOTEND") (pin "4") (pinfunction "4_4") (pintype "passive"))
      (node (ref "PWR") (pin "1") (pinfunction "S_1") (pintype "passive"))
      (node (ref "PWR") (pin "2") (pinfunction "S_2") (pintype "passive"))
      (node (ref "PWR") (pin "3") (pinfunction "S_3") (pintype "passive"))
      (node (ref "U1") (pin "4") (pinfunction "~{SHDN}_4") (pintype "input"))
      (node (ref "U1") (pin "5") (pinfunction "VIN_5") (pintype "power_in"))
      (node (ref "U2") (pin "16") (pinfunction "VBB1_16") (pintype "power_in"))
      (node (ref "U2") (pin "21") (pinfunction "VBB2_21") (pintype "power_in"))
      (node (ref "U3") (pin "16") (pinfunction "VBB1_16") (pintype "power_in"))
      (node (ref "U3") (pin "21") (pinfunction "VBB2_21") (pintype "power_in"))
      (node (ref "U4") (pin "16") (pinfunction "VBB1_16") (pintype "power_in"))
      (node (ref "U4") (pin "21") (pinfunction "VBB2_21") (pintype "power_in"))
      (node (ref "U5") (pin "16") (pinfunction "VBB1_16") (pintype "power_in"))
      (node (ref "U5") (pin "21") (pinfunction "VBB2_21") (pintype "power_in"))
      (node (ref "Z-STOP") (pin "2") (pinfunction "2_2") (pintype "passive"))
    )
    (net (code "66") (name "GND") (class "Default")
      (node (ref "BOOT") (pin "1") (pinfunction "1_1") (pintype "passive"))
      (node (ref "C1") (pin "2") (pinfunction "2_2") (pintype "passive"))
      (node (ref "C10") (pin "1") (pinfunction "1_1") (pintype "passive"))
      (node (ref "C11") (pin "1") (pinfunction "1_1") (pintype "passive"))
      (node (ref "C12") (pin "2") (pinfunction "2_2") (pintype "passive"))
      (node (ref "C13") (pin "1") (pinfunction "1_1") (pintype "passive"))
      (node (ref "C14") (pin "2") (pinfunction "2_2") (pintype "passive"))
      (node (ref "C15") (pin "1") (pinfunction "1_1") (pintype "passive"))
      (node (ref "C16") (pin "-") (pinfunction "-_-") (pintype "passive"))
      (node (ref "C18") (pin "-") (pinfunction "-_-") (pintype "passive"))
      (node (ref "C19") (pin "1") (pinfunction "1_1") (pintype "passive"))
      (node (ref "C20") (pin "1") (pinfunction "1_1") (pintype "passive"))
      (node (ref "C23") (pin "-") (pinfunction "-_-") (pintype "passive"))
      (node (ref "C24") (pin "1") (pinfunction "1_1") (pintype "passive"))
      (node (ref "C25") (pin "1") (pinfunction "1_1") (pintype "passive"))
      (node (ref "C28") (pin "2") (pinfunction "2_2") (pintype "passive"))
      (node (ref "C29") (pin "1") (pinfunction "1_1") (pintype "passive"))
      (node (ref "C3") (pin "2") (pinfunction "2_2") (pintype "passive"))
      (node (ref "C30") (pin "1") (pinfunction "1_1") (pintype "passive"))
      (node (ref "C32") (pin "2") (pinfunction "2_2") (pintype "passive"))
      (node (ref "C33") (pin "2") (pinfunction "2_2") (pintype "passive"))
      (node (ref "C34") (pin "1") (pinfunction "1_1") (pintype "passive"))
      (node (ref "C35") (pin "2") (pinfunction "2_2") (pintype "passive"))
      (node (ref "C36") (pin "1") (pinfunction "1_1") (pintype "passive"))
      (node (ref "C37") (pin "2") (pinfunction "2_2") (pintype "passive"))
      (node (ref "C38") (pin "2") (pinfunction "2_2") (pintype "passive"))
      (node (ref "C39") (pin "2") (pinfunction "2_2") (pintype "passive"))
      (node (ref "C40") (pin "2") (pinfunction "2_2") (pintype "passive"))
      (node (ref "C41") (pin "2") (pinfunction "2_2") (pintype "passive"))
      (node (ref "C42") (pin "1") (pinfunction "1_1") (pintype "passive"))
      (node (ref "C43") (pin "1") (pinfunction "1_1") (pintype "passive"))
      (node (ref "C44") (pin "1") (pinfunction "1_1") (pintype "passive"))
      (node (ref "C6") (pin "-") (pinfunction "-_-") (pintype "passive"))
      (node (ref "C7") (pin "-") (pinfunction "-_-") (pintype "passive"))
      (node (ref "C8") (pin "1") (pinfunction "1_1") (pintype "passive"))
      (node (ref "C9") (pin "1") (pinfunction "1_1") (pintype "passive"))
      (node (ref "D1") (pin "A") (pinfunction "A_A") (pintype "passive"))
      (node (ref "D2") (pin "A") (pinfunction "A_A") (pintype "passive"))
      (node (ref "D3") (pin "A") (pinfunction "A_A") (pintype "passive"))
      (node (ref "EXP1") (pin "14") (pinfunction "14_14") (pintype "passive"))
      (node (ref "EXP2") (pin "1") (pinfunction "1_1") (pintype "passive"))
      (node (ref "ICSP") (pin "1") (pinfunction "1_1") (pintype "passive"))
      (node (ref "LED1") (pin "C") (pinfunction "C_C") (pintype "passive"))
      (node (ref "PWR") (pin "4") (pinfunction "S_4") (pintype "passive"))
      (node (ref "PWR") (pin "5") (pinfunction "S_5") (pintype "passive"))
      (node (ref "PWR") (pin "6") (pinfunction "S_6") (pintype "passive"))
      (node (ref "Q1") (pin "3") (pinfunction "S_3") (pintype "passive"))
      (node (ref "Q2") (pin "3") (pinfunction "S_3") (pintype "passive"))
      (node (ref "Q3") (pin "2") (pinfunction "S_2") (pintype "passive"))
      (node (ref "Q4") (pin "2") (pinfunction "S_2") (pintype "passive"))
      (node (ref "Q5") (pin "2") (pinfunction "S_2") (pintype "passive"))
      (node (ref "R14") (pin "2") (pinfunction "2_2") (pintype "passive"))
      (node (ref "R16") (pin "2") (pinfunction "2_2") (pintype "passive"))
      (node (ref "R17") (pin "2") (pinfunction "2_2") (pintype "passive"))
      (node (ref "R18") (pin "2") (pinfunction "2_2") (pintype "passive"))
      (node (ref "R19") (pin "2") (pinfunction "2_2") (pintype "passive"))
      (node (ref "R2") (pin "2") (pinfunction "2_2") (pintype "passive"))
      (node (ref "R20") (pin "2") (pinfunction "2_2") (pintype "passive"))
      (node (ref "R23") (pin "2") (pinfunction "2_2") (pintype "passive"))
      (node (ref "R24") (pin "2") (pinfunction "2_2") (pintype "passive"))
      (node (ref "R25") (pin "2") (pinfunction "2_2") (pintype "passive"))
      (node (ref "R26") (pin "2") (pinfunction "2_2") (pintype "passive"))
      (node (ref "R30") (pin "2") (pinfunction "2_2") (pintype "passive"))
      (node (ref "R31") (pin "2") (pinfunction "2_2") (pintype "passive"))
      (node (ref "R32") (pin "2") (pinfunction "2_2") (pintype "passive"))
      (node (ref "R35") (pin "2") (pinfunction "2_2") (pintype "passive"))
      (node (ref "R38") (pin "2") (pinfunction "2_2") (pintype "passive"))
      (node (ref "R6") (pin "2") (pinfunction "2_2") (pintype "passive"))
      (node (ref "S1") (pin "B2") (pinfunction "2_B2") (pintype "passive"))
      (node (ref "SD") (pin "GND1") (pinfunction "SHEILD_GND1") (pintype "power_in"))
      (node (ref "SD") (pin "GND2") (pinfunction "SHIELD_GND2") (pintype "power_in"))
      (node (ref "SD") (pin "GND3") (pinfunction "SHIELD_GND3") (pintype "power_in"))
      (node (ref "SD") (pin "P$6") (pinfunction "GND_P$6") (pintype "power_in"))
      (node (ref "T-BED") (pin "2") (pinfunction "2_2") (pintype "passive"))
      (node (ref "T-EXT") (pin "2") (pinfunction "2_2") (pintype "passive"))
      (node (ref "U1") (pin "2") (pinfunction "GND_2") (pintype "power_in"))
      (node (ref "U10") (pin "10") (pinfunction "VSS_10") (pintype "power_in"))
      (node (ref "U2") (pin "13") (pinfunction "GND1_13") (pintype "power_in"))
      (node (ref "U2") (pin "24") (pinfunction "GND2_24") (pintype "power_in"))
      (node (ref "U2") (pin "PAD") (pinfunction "PAD_PAD") (pintype "power_in"))
      (node (ref "U3") (pin "13") (pinfunction "GND1_13") (pintype "power_in"))
      (node (ref "U3") (pin "24") (pinfunction "GND2_24") (pintype "power_in"))
      (node (ref "U3") (pin "PAD") (pinfunction "PAD_PAD") (pintype "power_in"))
      (node (ref "U4") (pin "13") (pinfunction "GND1_13") (pintype "power_in"))
      (node (ref "U4") (pin "24") (pinfunction "GND2_24") (pintype "power_in"))
      (node (ref "U4") (pin "PAD") (pinfunction "PAD_PAD") (pintype "power_in"))
      (node (ref "U5") (pin "13") (pinfunction "GND1_13") (pintype "power_in"))
      (node (ref "U5") (pin "24") (pinfunction "GND2_24") (pintype "power_in"))
      (node (ref "U5") (pin "PAD") (pinfunction "PAD_PAD") (pintype "power_in"))
      (node (ref "U6") (pin "22") (pinfunction "GND_22") (pintype "power_in"))
      (node (ref "U6") (pin "53") (pinfunction "GND_53") (pintype "power_in"))
      (node (ref "U6") (pin "6") (pinfunction "UGND_6") (pintype "power_in"))
      (node (ref "U6") (pin "63") (pinfunction "AGND_63") (pintype "power_in"))
      (node (ref "U7") (pin "3") (pinfunction "GND_3") (pintype "power_in"))
      (node (ref "U8") (pin "7") (pinfunction "GND_7") (pintype "power_in"))
      (node (ref "U9") (pin "2") (pinfunction "GND_2") (pintype "power_in"))
      (node (ref "USB-M") (pin "GND") (pinfunction "GND_GND") (pintype "bidirectional"))
      (node (ref "USB-M") (pin "GND1") (pinfunction "GND_GND1") (pintype "bidirectional"))
      (node (ref "USB-M") (pin "GND2") (pinfunction "GND_GND2") (pintype "bidirectional"))
      (node (ref "USB-M") (pin "GND3") (pinfunction "GND_GND3") (pintype "bidirectional"))
      (node (ref "USB-M") (pin "GND4") (pinfunction "GND_GND4") (pintype "bidirectional"))
      (node (ref "USB-M") (pin "GND5") (pinfunction "GND_GND5") (pintype "bidirectional"))
      (node (ref "USB-M") (pin "GND6") (pinfunction "GND_GND6") (pintype "bidirectional"))
      (node (ref "USB-M") (pin "GND7") (pinfunction "GND_GND7") (pintype "bidirectional"))
      (node (ref "USB-M") (pin "GND8") (pinfunction "GND_GND8") (pintype "bidirectional"))
      (node (ref "X-STOP") (pin "3") (pinfunction "3_3") (pintype "passive"))
      (node (ref "Y-STOP") (pin "3") (pinfunction "3_3") (pintype "passive"))
      (node (ref "Z-STOP") (pin "3") (pinfunction "3_3") (pintype "passive"))
    )
    (net (code "67") (name "Net-(HOTBEDB-S)") (class "Default")
      (node (ref "HOTBED") (pin "P$2") (pinfunction "S_P$2") (pintype "passive"))
      (node (ref "Q2") (pin "2") (pinfunction "D_2") (pintype "passive"))
    )
    (net (code "68") (name "Net-(L1-1)") (class "Default")
      (node (ref "C2") (pin "1") (pinfunction "1_1") (pintype "passive"))
      (node (ref "D1") (pin "C") (pinfunction "C_C") (pintype "passive"))
      (node (ref "L1") (pin "P$1") (pinfunction "1_P$1") (pintype "passive"))
      (node (ref "U1") (pin "6") (pinfunction "SW_6") (pintype "passive"))
    )
    (net (code "69") (name "Net-(LED1-PadA)") (class "Default")
      (node (ref "LED1") (pin "A") (pinfunction "A_A") (pintype "passive"))
      (node (ref "R1") (pin "1") (pinfunction "1_1") (pintype "passive"))
    )
    (net (code "70") (name "Net-(Q1-D)") (class "Default")
      (node (ref "HOTEND") (pin "1") (pinfunction "1_1") (pintype "passive"))
      (node (ref "HOTEND") (pin "2") (pinfunction "2_2") (pintype "passive"))
      (node (ref "Q1") (pin "2") (pinfunction "D_2") (pintype "passive"))
    )
    (net (code "71") (name "Net-(Q1-G)") (class "Default")
      (node (ref "Q1") (pin "1") (pinfunction "G_1") (pintype "passive"))
      (node (ref "R36") (pin "2") (pinfunction "2_2") (pintype "passive"))
    )
    (net (code "72") (name "Net-(Q2-G)") (class "Default")
      (node (ref "Q2") (pin "1") (pinfunction "G_1") (pintype "passive"))
      (node (ref "R11") (pin "2") (pinfunction "2_2") (pintype "passive"))
    )
    (net (code "73") (name "Net-(Q3-D)") (class "Default")
      (node (ref "D2") (pin "C") (pinfunction "C_C") (pintype "passive"))
      (node (ref "FAN1") (pin "2") (pinfunction "2_2") (pintype "passive"))
      (node (ref "Q3") (pin "3") (pinfunction "D_3") (pintype "passive"))
    )
    (net (code "74") (name "Net-(Q4-G)") (class "Default")
      (node (ref "Q4") (pin "1") (pinfunction "G_1") (pintype "passive"))
      (node (ref "Z-STOP") (pin "1") (pinfunction "1_1") (pintype "passive"))
    )
    (net (code "75") (name "Net-(Q5-D)") (class "Default")
      (node (ref "D3") (pin "C") (pinfunction "C_C") (pintype "passive"))
      (node (ref "FAN2") (pin "2") (pinfunction "2_2") (pintype "passive"))
      (node (ref "Q5") (pin "3") (pinfunction "D_3") (pintype "passive"))
    )
    (net (code "76") (name "Net-(U1-CB)") (class "Default")
      (node (ref "C2") (pin "2") (pinfunction "2_2") (pintype "passive"))
      (node (ref "U1") (pin "1") (pinfunction "CB_1") (pintype "passive"))
    )
    (net (code "77") (name "Net-(U1-FB)") (class "Default")
      (node (ref "R37") (pin "2") (pinfunction "2_2") (pintype "passive"))
      (node (ref "R38") (pin "1") (pinfunction "1_1") (pintype "passive"))
      (node (ref "U1") (pin "3") (pinfunction "FB_3") (pintype "passive"))
    )
    (net (code "78") (name "Net-(U2-CP1)") (class "Default")
      (node (ref "C5") (pin "2") (pinfunction "2_2") (pintype "passive"))
      (node (ref "U2") (pin "1") (pinfunction "CP1_1") (pintype "passive"))
    )
    (net (code "79") (name "Net-(U2-CP2)") (class "Default")
      (node (ref "C5") (pin "1") (pinfunction "1_1") (pintype "passive"))
      (node (ref "U2") (pin "2") (pinfunction "CP2_2") (pintype "passive"))
    )
    (net (code "80") (name "Net-(U2-MS1)") (class "Default")
      (node (ref "MS-X") (pin "1") (pinfunction "1_1") (pintype "passive"))
      (node (ref "U2") (pin "5") (pinfunction "MS1_5") (pintype "input"))
    )
    (net (code "81") (name "Net-(U2-MS2)") (class "Default")
      (node (ref "MS-X") (pin "3") (pinfunction "3_3") (pintype "passive"))
      (node (ref "U2") (pin "6") (pinfunction "MS2_6") (pintype "input"))
    )
    (net (code "82") (name "Net-(U2-OUT1A)") (class "Default")
      (node (ref "U2") (pin "18") (pinfunction "OUT1A_18") (pintype "output"))
      (node (ref "X-MOT") (pin "3") (pinfunction "3_3") (pintype "passive"))
    )
    (net (code "83") (name "Net-(U2-OUT1B)") (class "Default")
      (node (ref "U2") (pin "15") (pinfunction "OUT1B_15") (pintype "output"))
      (node (ref "X-MOT") (pin "4") (pinfunction "4_4") (pintype "passive"))
    )
    (net (code "84") (name "Net-(U2-OUT2A)") (class "Default")
      (node (ref "U2") (pin "19") (pinfunction "OUT2A_19") (pintype "output"))
      (node (ref "X-MOT") (pin "2") (pinfunction "2_2") (pintype "passive"))
    )
    (net (code "85") (name "Net-(U2-OUT2B)") (class "Default")
      (node (ref "U2") (pin "22") (pinfunction "OUT2B_22") (pintype "output"))
      (node (ref "X-MOT") (pin "1") (pinfunction "1_1") (pintype "passive"))
    )
    (net (code "86") (name "Net-(U2-ROSC)") (class "Default")
      (node (ref "R2") (pin "1") (pinfunction "1_1") (pintype "passive"))
      (node (ref "U2") (pin "8") (pinfunction "ROSC_8") (pintype "passive"))
    )
    (net (code "87") (name "Net-(U2-SENSE1)") (class "Default")
      (node (ref "R17") (pin "1") (pinfunction "1_1") (pintype "passive"))
      (node (ref "U2") (pin "17") (pinfunction "SENSE1_17") (pintype "passive"))
    )
    (net (code "88") (name "Net-(U2-SENSE2)") (class "Default")
      (node (ref "R18") (pin "1") (pinfunction "1_1") (pintype "passive"))
      (node (ref "U2") (pin "20") (pinfunction "SENSE2_20") (pintype "passive"))
    )
    (net (code "89") (name "Net-(U2-VCP)") (class "Default")
      (node (ref "C4") (pin "2") (pinfunction "2_2") (pintype "passive"))
      (node (ref "U2") (pin "3") (pinfunction "VCP_3") (pintype "passive"))
    )
    (net (code "90") (name "Net-(U2-VREG)") (class "Default")
      (node (ref "C8") (pin "2") (pinfunction "2_2") (pintype "passive"))
      (node (ref "U2") (pin "4") (pinfunction "VREG_4") (pintype "passive"))
    )
    (net (code "91") (name "Net-(U2-~{RESET})") (class "Default")
      (node (ref "R4") (pin "2") (pinfunction "2_2") (pintype "passive"))
      (node (ref "U2") (pin "7") (pinfunction "~{RESET}_7") (pintype "input"))
      (node (ref "U2") (pin "9") (pinfunction "~{SLEEP}_9") (pintype "input"))
    )
    (net (code "92") (name "Net-(U3-CP1)") (class "Default")
      (node (ref "C17") (pin "2") (pinfunction "2_2") (pintype "passive"))
      (node (ref "U3") (pin "1") (pinfunction "CP1_1") (pintype "passive"))
    )
    (net (code "93") (name "Net-(U3-CP2)") (class "Default")
      (node (ref "C17") (pin "1") (pinfunction "1_1") (pintype "passive"))
      (node (ref "U3") (pin "2") (pinfunction "CP2_2") (pintype "passive"))
    )
    (net (code "94") (name "Net-(U3-MS1)") (class "Default")
      (node (ref "MS-Y") (pin "1") (pinfunction "1_1") (pintype "passive"))
      (node (ref "U3") (pin "5") (pinfunction "MS1_5") (pintype "input"))
    )
    (net (code "95") (name "Net-(U3-MS2)") (class "Default")
      (node (ref "MS-Y") (pin "3") (pinfunction "3_3") (pintype "passive"))
      (node (ref "U3") (pin "6") (pinfunction "MS2_6") (pintype "input"))
    )
    (net (code "96") (name "Net-(U3-OUT1A)") (class "Default")
      (node (ref "U3") (pin "18") (pinfunction "OUT1A_18") (pintype "output"))
      (node (ref "Y-MOT") (pin "3") (pinfunction "3_3") (pintype "passive"))
    )
    (net (code "97") (name "Net-(U3-OUT1B)") (class "Default")
      (node (ref "U3") (pin "15") (pinfunction "OUT1B_15") (pintype "output"))
      (node (ref "Y-MOT") (pin "4") (pinfunction "4_4") (pintype "passive"))
    )
    (net (code "98") (name "Net-(U3-OUT2A)") (class "Default")
      (node (ref "U3") (pin "19") (pinfunction "OUT2A_19") (pintype "output"))
      (node (ref "Y-MOT") (pin "2") (pinfunction "2_2") (pintype "passive"))
    )
    (net (code "99") (name "Net-(U3-OUT2B)") (class "Default")
      (node (ref "U3") (pin "22") (pinfunction "OUT2B_22") (pintype "output"))
      (node (ref "Y-MOT") (pin "1") (pinfunction "1_1") (pintype "passive"))
    )
    (net (code "100") (name "Net-(U3-ROSC)") (class "Default")
      (node (ref "R20") (pin "1") (pinfunction "1_1") (pintype "passive"))
      (node (ref "U3") (pin "8") (pinfunction "ROSC_8") (pintype "passive"))
    )
    (net (code "101") (name "Net-(U3-SENSE1)") (class "Default")
      (node (ref "R16") (pin "1") (pinfunction "1_1") (pintype "passive"))
      (node (ref "U3") (pin "17") (pinfunction "SENSE1_17") (pintype "passive"))
    )
    (net (code "102") (name "Net-(U3-SENSE2)") (class "Default")
      (node (ref "R19") (pin "1") (pinfunction "1_1") (pintype "passive"))
      (node (ref "U3") (pin "20") (pinfunction "SENSE2_20") (pintype "passive"))
    )
    (net (code "103") (name "Net-(U3-VCP)") (class "Default")
      (node (ref "C21") (pin "2") (pinfunction "2_2") (pintype "passive"))
      (node (ref "U3") (pin "3") (pinfunction "VCP_3") (pintype "passive"))
    )
    (net (code "104") (name "Net-(U3-VREG)") (class "Default")
      (node (ref "C19") (pin "2") (pinfunction "2_2") (pintype "passive"))
      (node (ref "U3") (pin "4") (pinfunction "VREG_4") (pintype "passive"))
    )
    (net (code "105") (name "Net-(U3-~{RESET})") (class "Default")
      (node (ref "R22") (pin "2") (pinfunction "2_2") (pintype "passive"))
      (node (ref "U3") (pin "7") (pinfunction "~{RESET}_7") (pintype "input"))
      (node (ref "U3") (pin "9") (pinfunction "~{SLEEP}_9") (pintype "input"))
    )
    (net (code "106") (name "Net-(U4-CP1)") (class "Default")
      (node (ref "C22") (pin "2") (pinfunction "2_2") (pintype "passive"))
      (node (ref "U4") (pin "1") (pinfunction "CP1_1") (pintype "passive"))
    )
    (net (code "107") (name "Net-(U4-CP2)") (class "Default")
      (node (ref "C22") (pin "1") (pinfunction "1_1") (pintype "passive"))
      (node (ref "U4") (pin "2") (pinfunction "CP2_2") (pintype "passive"))
    )
    (net (code "108") (name "Net-(U4-MS1)") (class "Default")
      (node (ref "MS-Z") (pin "1") (pinfunction "1_1") (pintype "passive"))
      (node (ref "U4") (pin "5") (pinfunction "MS1_5") (pintype "input"))
    )
    (net (code "109") (name "Net-(U4-MS2)") (class "Default")
      (node (ref "MS-Z") (pin "3") (pinfunction "3_3") (pintype "passive"))
      (node (ref "U4") (pin "6") (pinfunction "MS2_6") (pintype "input"))
    )
    (net (code "110") (name "Net-(U4-OUT1A)") (class "Default")
      (node (ref "U4") (pin "18") (pinfunction "OUT1A_18") (pintype "output"))
      (node (ref "Z-MOT") (pin "3") (pinfunction "3_3") (pintype "passive"))
    )
    (net (code "111") (name "Net-(U4-OUT1B)") (class "Default")
      (node (ref "U4") (pin "15") (pinfunction "OUT1B_15") (pintype "output"))
      (node (ref "Z-MOT") (pin "4") (pinfunction "4_4") (pintype "passive"))
    )
    (net (code "112") (name "Net-(U4-OUT2A)") (class "Default")
      (node (ref "U4") (pin "19") (pinfunction "OUT2A_19") (pintype "output"))
      (node (ref "Z-MOT") (pin "2") (pinfunction "2_2") (pintype "passive"))
    )
    (net (code "113") (name "Net-(U4-OUT2B)") (class "Default")
      (node (ref "U4") (pin "22") (pinfunction "OUT2B_22") (pintype "output"))
      (node (ref "Z-MOT") (pin "1") (pinfunction "1_1") (pintype "passive"))
    )
    (net (code "114") (name "Net-(U4-ROSC)") (class "Default")
      (node (ref "R26") (pin "1") (pinfunction "1_1") (pintype "passive"))
      (node (ref "U4") (pin "8") (pinfunction "ROSC_8") (pintype "passive"))
    )
    (net (code "115") (name "Net-(U4-SENSE1)") (class "Default")
      (node (ref "R24") (pin "1") (pinfunction "1_1") (pintype "passive"))
      (node (ref "U4") (pin "17") (pinfunction "SENSE1_17") (pintype "passive"))
    )
    (net (code "116") (name "Net-(U4-SENSE2)") (class "Default")
      (node (ref "R25") (pin "1") (pinfunction "1_1") (pintype "passive"))
      (node (ref "U4") (pin "20") (pinfunction "SENSE2_20") (pintype "passive"))
    )
    (net (code "117") (name "Net-(U4-VCP)") (class "Default")
      (node (ref "C26") (pin "2") (pinfunction "2_2") (pintype "passive"))
      (node (ref "U4") (pin "3") (pinfunction "VCP_3") (pintype "passive"))
    )
    (net (code "118") (name "Net-(U4-VREG)") (class "Default")
      (node (ref "C24") (pin "2") (pinfunction "2_2") (pintype "passive"))
      (node (ref "U4") (pin "4") (pinfunction "VREG_4") (pintype "passive"))
    )
    (net (code "119") (name "Net-(U4-~{RESET})") (class "Default")
      (node (ref "R28") (pin "2") (pinfunction "2_2") (pintype "passive"))
      (node (ref "U4") (pin "7") (pinfunction "~{RESET}_7") (pintype "input"))
      (node (ref "U4") (pin "9") (pinfunction "~{SLEEP}_9") (pintype "input"))
    )
    (net (code "120") (name "Net-(U5-CP1)") (class "Default")
      (node (ref "C27") (pin "2") (pinfunction "2_2") (pintype "passive"))
      (node (ref "U5") (pin "1") (pinfunction "CP1_1") (pintype "passive"))
    )
    (net (code "121") (name "Net-(U5-CP2)") (class "Default")
      (node (ref "C27") (pin "1") (pinfunction "1_1") (pintype "passive"))
      (node (ref "U5") (pin "2") (pinfunction "CP2_2") (pintype "passive"))
    )
    (net (code "122") (name "Net-(U5-MS1)") (class "Default")
      (node (ref "MS-E") (pin "1") (pinfunction "1_1") (pintype "passive"))
      (node (ref "U5") (pin "5") (pinfunction "MS1_5") (pintype "input"))
    )
    (net (code "123") (name "Net-(U5-MS2)") (class "Default")
      (node (ref "MS-E") (pin "3") (pinfunction "3_3") (pintype "passive"))
      (node (ref "U5") (pin "6") (pinfunction "MS2_6") (pintype "input"))
    )
    (net (code "124") (name "Net-(U5-OUT1A)") (class "Default")
      (node (ref "E-MOT") (pin "3") (pinfunction "3_3") (pintype "passive"))
      (node (ref "U5") (pin "18") (pinfunction "OUT1A_18") (pintype "output"))
    )
    (net (code "125") (name "Net-(U5-OUT1B)") (class "Default")
      (node (ref "E-MOT") (pin "4") (pinfunction "4_4") (pintype "passive"))
      (node (ref "U5") (pin "15") (pinfunction "OUT1B_15") (pintype "output"))
    )
    (net (code "126") (name "Net-(U5-OUT2A)") (class "Default")
      (node (ref "E-MOT") (pin "2") (pinfunction "2_2") (pintype "passive"))
      (node (ref "U5") (pin "19") (pinfunction "OUT2A_19") (pintype "output"))
    )
    (net (code "127") (name "Net-(U5-OUT2B)") (class "Default")
      (node (ref "E-MOT") (pin "1") (pinfunction "1_1") (pintype "passive"))
      (node (ref "U5") (pin "22") (pinfunction "OUT2B_22") (pintype "output"))
    )
    (net (code "128") (name "Net-(U5-ROSC)") (class "Default")
      (node (ref "R32") (pin "1") (pinfunction "1_1") (pintype "passive"))
      (node (ref "U5") (pin "8") (pinfunction "ROSC_8") (pintype "passive"))
    )
    (net (code "129") (name "Net-(U5-SENSE1)") (class "Default")
      (node (ref "R30") (pin "1") (pinfunction "1_1") (pintype "passive"))
      (node (ref "U5") (pin "17") (pinfunction "SENSE1_17") (pintype "passive"))
    )
    (net (code "130") (name "Net-(U5-SENSE2)") (class "Default")
      (node (ref "R31") (pin "1") (pinfunction "1_1") (pintype "passive"))
      (node (ref "U5") (pin "20") (pinfunction "SENSE2_20") (pintype "passive"))
    )
    (net (code "131") (name "Net-(U5-VCP)") (class "Default")
      (node (ref "C31") (pin "2") (pinfunction "2_2") (pintype "passive"))
      (node (ref "U5") (pin "3") (pinfunction "VCP_3") (pintype "passive"))
    )
    (net (code "132") (name "Net-(U5-VREG)") (class "Default")
      (node (ref "C29") (pin "2") (pinfunction "2_2") (pintype "passive"))
      (node (ref "U5") (pin "4") (pinfunction "VREG_4") (pintype "passive"))
    )
    (net (code "133") (name "Net-(U5-~{RESET})") (class "Default")
      (node (ref "R34") (pin "2") (pinfunction "2_2") (pintype "passive"))
      (node (ref "U5") (pin "7") (pinfunction "~{RESET}_7") (pintype "input"))
      (node (ref "U5") (pin "9") (pinfunction "~{SLEEP}_9") (pintype "input"))
    )
    (net (code "134") (name "Net-(U6-AREF)") (class "Default")
      (node (ref "C3") (pin "1") (pinfunction "1_1") (pintype "passive"))
      (node (ref "U6") (pin "62") (pinfunction "AREF_62") (pintype "power_in"))
    )
    (net (code "135") (name "Net-(U6-D+)") (class "Default")
      (node (ref "R8") (pin "2") (pinfunction "2_2") (pintype "passive"))
      (node (ref "U6") (pin "5") (pinfunction "D+_5") (pintype "bidirectional"))
    )
    (net (code "136") (name "Net-(U6-D-)") (class "Default")
      (node (ref "R7") (pin "2") (pinfunction "2_2") (pintype "passive"))
      (node (ref "U6") (pin "4") (pinfunction "D-_4") (pintype "bidirectional"))
    )
    (net (code "137") (name "Net-(U6-UCAP)") (class "Default")
      (node (ref "C11") (pin "2") (pinfunction "2_2") (pintype "passive"))
      (node (ref "U6") (pin "7") (pinfunction "UCAP_7") (pintype "power_in"))
    )
    (net (code "138") (name "unconnected-(EXP1-Pad9)") (class "Default")
      (node (ref "EXP1") (pin "9") (pinfunction "9_9") (pintype "passive"))
    )
    (net (code "139") (name "unconnected-(EXP1-Pad10)") (class "Default")
      (node (ref "EXP1") (pin "10") (pinfunction "10_10") (pintype "passive"))
    )
    (net (code "140") (name "unconnected-(EXP2-Pad3)") (class "Default")
      (node (ref "EXP2") (pin "3") (pinfunction "3_3") (pintype "passive"))
    )
    (net (code "141") (name "unconnected-(EXP2-Pad4)") (class "Default")
      (node (ref "EXP2") (pin "4") (pinfunction "4_4") (pintype "passive"))
    )
    (net (code "142") (name "unconnected-(EXP2-Pad9)") (class "Default")
      (node (ref "EXP2") (pin "9") (pinfunction "9_9") (pintype "passive"))
    )
    (net (code "143") (name "unconnected-(SD-DAT1-PadP$8)") (class "Default")
      (node (ref "SD") (pin "P$8") (pinfunction "DAT1_P$8") (pintype "bidirectional"))
    )
    (net (code "144") (name "unconnected-(SD-DAT2-PadP$1)") (class "Default")
      (node (ref "SD") (pin "P$1") (pinfunction "DAT2_P$1") (pintype "bidirectional"))
    )
    (net (code "145") (name "unconnected-(U9-IO3-Pad4)") (class "Default")
      (node (ref "U9") (pin "4") (pinfunction "IO3_4") (pintype "bidirectional"))
    )
    (net (code "146") (name "unconnected-(U9-IO4-Pad6)") (class "Default")
      (node (ref "U9") (pin "6") (pinfunction "IO4_6") (pintype "bidirectional"))
    )
    (net (code "147") (name "unconnected-(U10-RDY{slash}~{BSY}-Pad5)") (class "Default")
      (node (ref "U10") (pin "5") (pinfunction "RDY/~{BSY}_5") (pintype "input"))
    )
  )
)
